# working.net
KiCad netlist of a schematic drawn in EAGLE
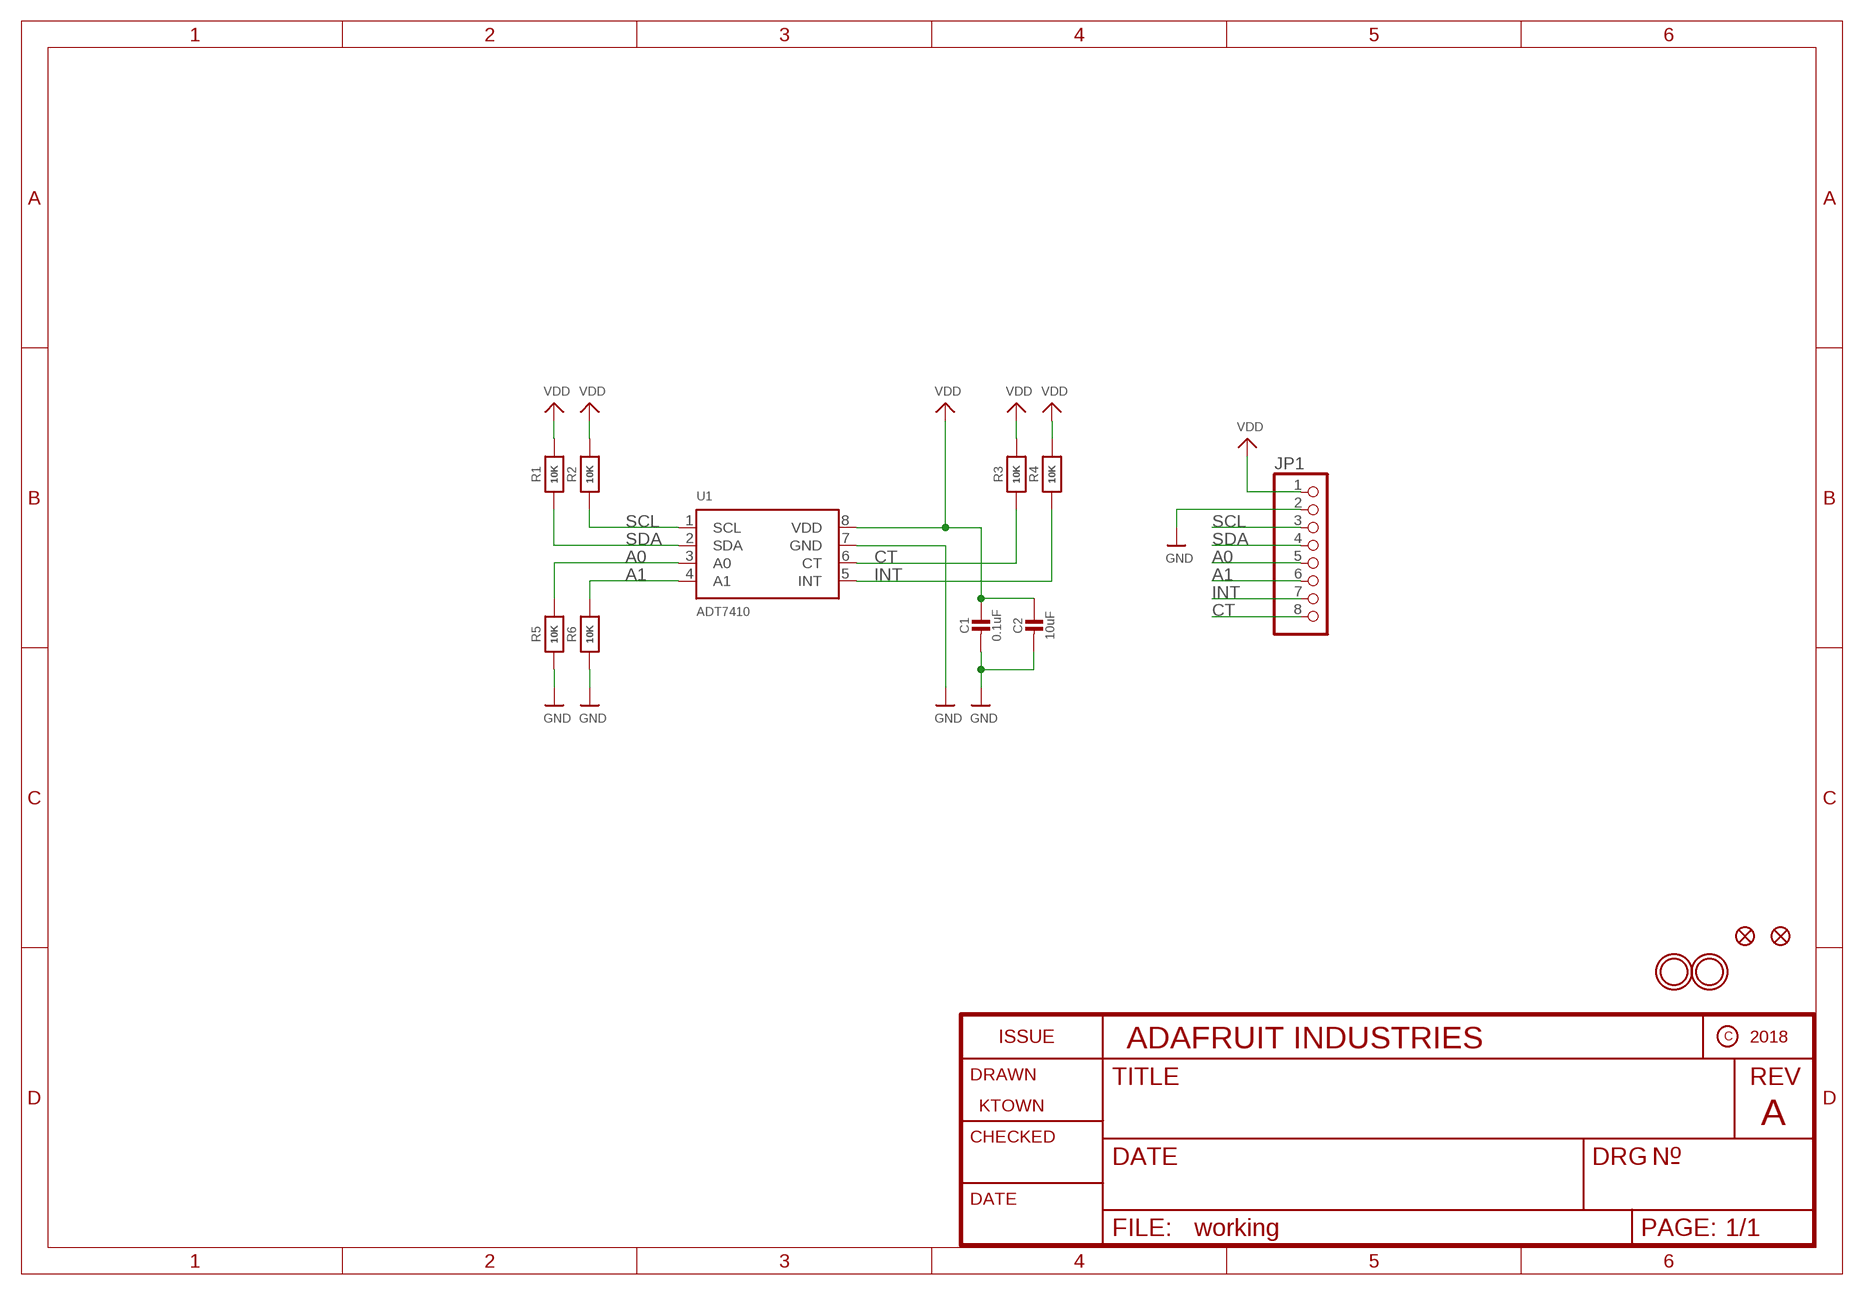
[diagram p0: schematic, sheet 1]

(export (version "E")
  (design (tool "Eeschema 10.0.6"))
  (components
    (comp (ref "C1")
      (value "0.1uF")
      (footprint "eagle-import:0603-NO")
      (libsource (lib "eagle-import") (part "CAP_CERAMIC0603_NO"))
    )
    (comp (ref "C2")
      (value "10uF")
      (footprint "eagle-import:0805-NO")
      (libsource (lib "eagle-import") (part "CAP_CERAMIC0805-NOOUTLINE"))
    )
    (comp (ref "FID1")
      (value "FIDUCIAL_1MM")
      (footprint "eagle-import:FIDUCIAL_1MM")
      (libsource (lib "eagle-import") (part "FIDUCIAL_1MM"))
    )
    (comp (ref "FID2")
      (value "FIDUCIAL_1MM")
      (footprint "eagle-import:FIDUCIAL_1MM")
      (libsource (lib "eagle-import") (part "FIDUCIAL_1MM"))
    )
    (comp (ref "JP1")
      (value "HEADER-1X870MIL")
      (footprint "eagle-import:1X08_ROUND_70")
      (libsource (lib "eagle-import") (part "HEADER-1X870MIL"))
    )
    (comp (ref "R1")
      (value "10K")
      (footprint "eagle-import:0603-NO")
      (libsource (lib "eagle-import") (part "RESISTOR_0603_NOOUT"))
    )
    (comp (ref "R2")
      (value "10K")
      (footprint "eagle-import:0603-NO")
      (libsource (lib "eagle-import") (part "RESISTOR_0603_NOOUT"))
    )
    (comp (ref "R3")
      (value "10K")
      (footprint "eagle-import:0603-NO")
      (libsource (lib "eagle-import") (part "RESISTOR_0603_NOOUT"))
    )
    (comp (ref "R4")
      (value "10K")
      (footprint "eagle-import:0603-NO")
      (libsource (lib "eagle-import") (part "RESISTOR_0603_NOOUT"))
    )
    (comp (ref "R5")
      (value "10K")
      (footprint "eagle-import:0603-NO")
      (libsource (lib "eagle-import") (part "RESISTOR_0603_NOOUT"))
    )
    (comp (ref "R6")
      (value "10K")
      (footprint "eagle-import:0603-NO")
      (libsource (lib "eagle-import") (part "RESISTOR_0603_NOOUT"))
    )
    (comp (ref "U$3")
      (value "MOUNTINGHOLE2.0")
      (footprint "eagle-import:MOUNTINGHOLE_2.0_PLATED")
      (libsource (lib "eagle-import") (part "MOUNTINGHOLE2.0"))
    )
    (comp (ref "U$4")
      (value "MOUNTINGHOLE2.0")
      (footprint "eagle-import:MOUNTINGHOLE_2.0_PLATED")
      (libsource (lib "eagle-import") (part "MOUNTINGHOLE2.0"))
    )
    (comp (ref "U1")
      (value "ADT7410")
      (footprint "eagle-import:SOIC8_150MIL")
      (libsource (lib "eagle-import") (part "TEMP_ADT7410"))
    )
  )
  (nets
    (net (code "1") (name "/A0") (class "Default")
      (node (ref "JP1") (pin "5") (pinfunction "5_5") (pintype "passive"))
      (node (ref "R5") (pin "2") (pinfunction "2_2") (pintype "passive"))
      (node (ref "U1") (pin "3") (pinfunction "A0_3") (pintype "bidirectional"))
    )
    (net (code "2") (name "/A1") (class "Default")
      (node (ref "JP1") (pin "6") (pinfunction "6_6") (pintype "passive"))
      (node (ref "R6") (pin "2") (pinfunction "2_2") (pintype "passive"))
      (node (ref "U1") (pin "4") (pinfunction "A1_4") (pintype "bidirectional"))
    )
    (net (code "3") (name "/CT") (class "Default")
      (node (ref "JP1") (pin "8") (pinfunction "8_8") (pintype "passive"))
      (node (ref "R3") (pin "1") (pinfunction "1_1") (pintype "passive"))
      (node (ref "U1") (pin "6") (pinfunction "CT_6") (pintype "bidirectional"))
    )
    (net (code "4") (name "/INT") (class "Default")
      (node (ref "JP1") (pin "7") (pinfunction "7_7") (pintype "passive"))
      (node (ref "R4") (pin "1") (pinfunction "1_1") (pintype "passive"))
      (node (ref "U1") (pin "5") (pinfunction "INT_5") (pintype "bidirectional"))
    )
    (net (code "5") (name "/SCL") (class "Default")
      (node (ref "JP1") (pin "3") (pinfunction "3_3") (pintype "passive"))
      (node (ref "R2") (pin "1") (pinfunction "1_1") (pintype "passive"))
      (node (ref "U1") (pin "1") (pinfunction "SCL_1") (pintype "bidirectional"))
    )
    (net (code "6") (name "/SDA") (class "Default")
      (node (ref "JP1") (pin "4") (pinfunction "4_4") (pintype "passive"))
      (node (ref "R1") (pin "1") (pinfunction "1_1") (pintype "passive"))
      (node (ref "U1") (pin "2") (pinfunction "SDA_2") (pintype "bidirectional"))
    )
    (net (code "7") (name "GND") (class "Default")
      (node (ref "C1") (pin "2") (pinfunction "2_2") (pintype "passive"))
      (node (ref "C2") (pin "2") (pinfunction "2_2") (pintype "passive"))
      (node (ref "JP1") (pin "2") (pinfunction "2_2") (pintype "passive"))
      (node (ref "R5") (pin "1") (pinfunction "1_1") (pintype "passive"))
      (node (ref "R6") (pin "1") (pinfunction "1_1") (pintype "passive"))
      (node (ref "U1") (pin "7") (pinfunction "GND_7") (pintype "power_in"))
    )
    (net (code "8") (name "VDD") (class "Default")
      (node (ref "C1") (pin "1") (pinfunction "1_1") (pintype "passive"))
      (node (ref "C2") (pin "1") (pinfunction "1_1") (pintype "passive"))
      (node (ref "JP1") (pin "1") (pinfunction "1_1") (pintype "passive"))
      (node (ref "R1") (pin "2") (pinfunction "2_2") (pintype "passive"))
      (node (ref "R2") (pin "2") (pinfunction "2_2") (pintype "passive"))
      (node (ref "R3") (pin "2") (pinfunction "2_2") (pintype "passive"))
      (node (ref "R4") (pin "2") (pinfunction "2_2") (pintype "passive"))
      (node (ref "U1") (pin "8") (pinfunction "VDD_8") (pintype "power_in"))
    )
  )
)
